# myversion.net
KiCad netlist of a schematic drawn in EAGLE
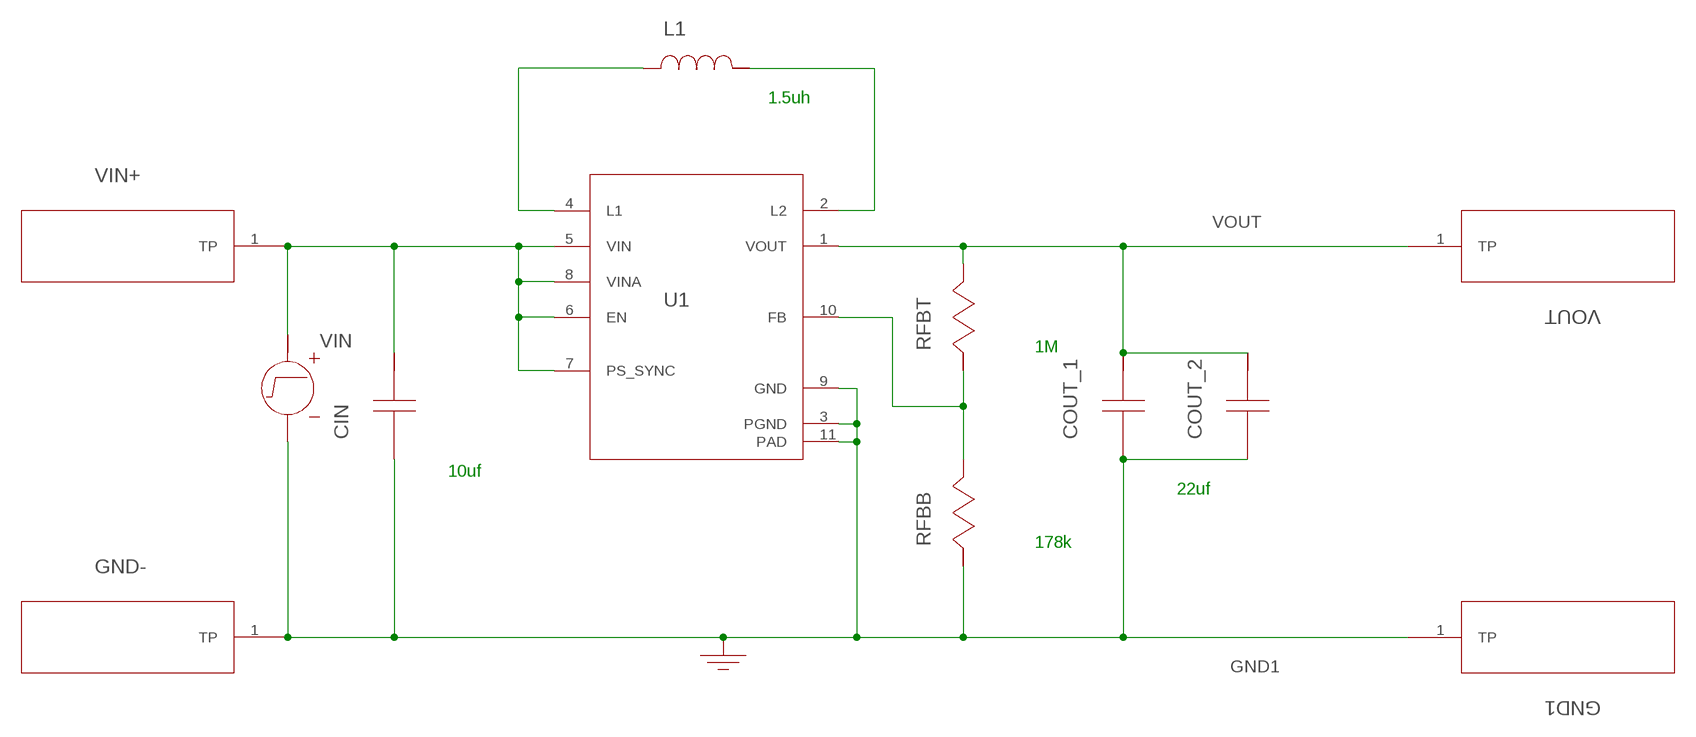
[diagram p0: schematic, sheet 1]

(export (version "E")
  (design (tool "Eeschema 10.0.6"))
  (components
    (comp (ref "CIN")
      (value "LMK212BJ106KG-T")
      (footprint "eagle-import:0805")
      (libsource (lib "eagle-import") (part "LMK212BJ106KG-T"))
    )
    (comp (ref "COUT_1")
      (value "LMK212BJ226MG-T")
      (footprint "eagle-import:0805")
      (libsource (lib "eagle-import") (part "LMK212BJ226MG-T"))
    )
    (comp (ref "COUT_2")
      (value "LMK212BJ226MG-T")
      (footprint "eagle-import:0805")
      (libsource (lib "eagle-import") (part "LMK212BJ226MG-T"))
    )
    (comp (ref "GND")
      (value "WB_GND")
      (footprint "eagle-import:WB_GND")
      (libsource (lib "eagle-import") (part "WB_GNDWB_GND"))
    )
    (comp (ref "GND-")
      (value "TP-1502")
      (footprint "eagle-import:TP-1502")
      (libsource (lib "eagle-import") (part "TP-1502"))
    )
    (comp (ref "GND1")
      (value "TP-1502")
      (footprint "eagle-import:TP-1502")
      (libsource (lib "eagle-import") (part "TP-1502"))
    )
    (comp (ref "L1")
      (value "LQM21PN1R5MC0D")
      (footprint "eagle-import:0805")
      (libsource (lib "eagle-import") (part "LQM21PN1R5MC0D"))
    )
    (comp (ref "RFBB")
      (value "CRCW0402178KFKED")
      (footprint "eagle-import:0402")
      (libsource (lib "eagle-import") (part "CRCW0402178KFKED"))
    )
    (comp (ref "RFBT")
      (value "CRCW04021M00FKED")
      (footprint "eagle-import:0402")
      (libsource (lib "eagle-import") (part "CRCW04021M00FKED"))
    )
    (comp (ref "U1")
      (value "TPS63000DRCR")
      (footprint "eagle-import:DRC0010J")
      (libsource (lib "eagle-import") (part "TPS63000DRCR"))
    )
    (comp (ref "VIN")
      (value "WB_STARTUP_VOLTAGE_SOURCE")
      (footprint "eagle-import:WB_STARTUP_VOLTAGE_SOURCE")
      (libsource (lib "eagle-import") (part "WB_STARTUP_VOLTAGE_SOURCEWB_STARTUP_VOLTAGE_SOURCE"))
    )
    (comp (ref "VIN+")
      (value "TP-1502")
      (footprint "eagle-import:TP-1502")
      (libsource (lib "eagle-import") (part "TP-1502"))
    )
    (comp (ref "VOUT")
      (value "TP-1502")
      (footprint "eagle-import:TP-1502")
      (libsource (lib "eagle-import") (part "TP-1502"))
    )
  )
  (nets
    (net (code "1") (name "/GND1") (class "Default")
      (node (ref "CIN") (pin "2") (pinfunction "2_2") (pintype "passive"))
      (node (ref "COUT_1") (pin "2") (pinfunction "2_2") (pintype "passive"))
      (node (ref "COUT_2") (pin "2") (pinfunction "2_2") (pintype "passive"))
      (node (ref "GND") (pin "1") (pinfunction "1_1") (pintype "passive"))
      (node (ref "GND-") (pin "1") (pinfunction "TP_1") (pintype "passive"))
      (node (ref "GND1") (pin "1") (pinfunction "TP_1") (pintype "passive"))
      (node (ref "RFBB") (pin "2") (pinfunction "2_2") (pintype "passive"))
      (node (ref "U1") (pin "11") (pinfunction "PAD_11") (pintype "power_in"))
      (node (ref "U1") (pin "3") (pinfunction "PGND_3") (pintype "power_in"))
      (node (ref "U1") (pin "9") (pinfunction "GND_9") (pintype "power_in"))
      (node (ref "VIN") (pin "2") (pinfunction "-_2") (pintype "passive"))
    )
    (net (code "2") (name "/VOUT") (class "Default")
      (node (ref "COUT_1") (pin "1") (pinfunction "1_1") (pintype "passive"))
      (node (ref "COUT_2") (pin "1") (pinfunction "1_1") (pintype "passive"))
      (node (ref "RFBT") (pin "1") (pinfunction "1_1") (pintype "passive"))
      (node (ref "U1") (pin "1") (pinfunction "VOUT_1") (pintype "power_in"))
      (node (ref "VOUT") (pin "1") (pinfunction "TP_1") (pintype "passive"))
    )
    (net (code "3") (name "Net-(U1-EN)") (class "Default")
      (node (ref "CIN") (pin "1") (pinfunction "1_1") (pintype "passive"))
      (node (ref "U1") (pin "5") (pinfunction "VIN_5") (pintype "power_in"))
      (node (ref "U1") (pin "6") (pinfunction "EN_6") (pintype "input"))
      (node (ref "U1") (pin "7") (pinfunction "PS_SYNC_7") (pintype "input"))
      (node (ref "U1") (pin "8") (pinfunction "VINA_8") (pintype "power_in"))
      (node (ref "VIN") (pin "1") (pinfunction "+_1") (pintype "passive"))
      (node (ref "VIN+") (pin "1") (pinfunction "TP_1") (pintype "passive"))
    )
    (net (code "4") (name "Net-(U1-FB)") (class "Default")
      (node (ref "RFBB") (pin "1") (pinfunction "1_1") (pintype "passive"))
      (node (ref "RFBT") (pin "2") (pinfunction "2_2") (pintype "passive"))
      (node (ref "U1") (pin "10") (pinfunction "FB_10") (pintype "input"))
    )
    (net (code "5") (name "Net-(U1-L1)") (class "Default")
      (node (ref "L1") (pin "1") (pinfunction "1_1") (pintype "passive"))
      (node (ref "U1") (pin "4") (pinfunction "L1_4") (pintype "passive"))
    )
    (net (code "6") (name "Net-(U1-L2)") (class "Default")
      (node (ref "L1") (pin "2") (pinfunction "2_2") (pintype "passive"))
      (node (ref "U1") (pin "2") (pinfunction "L2_2") (pintype "passive"))
    )
  )
)
